# J1.net
KiCad netlist of a schematic drawn in Altium Designer
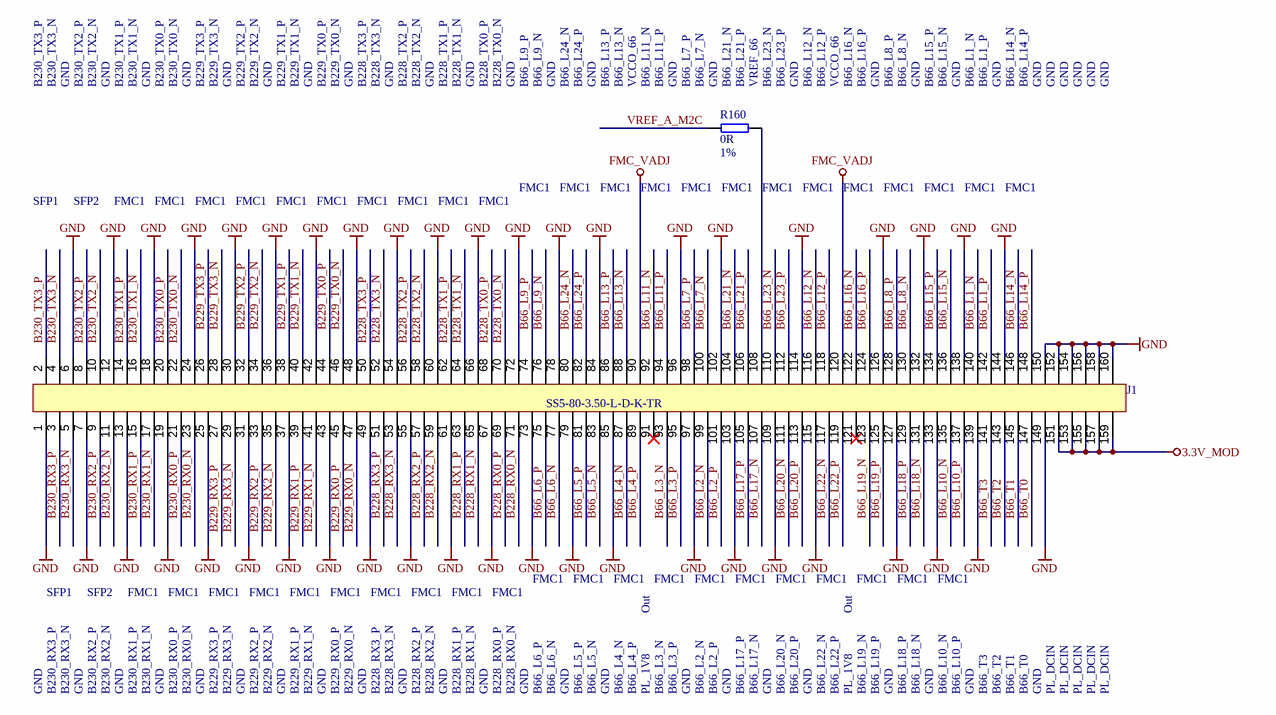
[diagram p0: J1.schdoc]

(export (version "E")
  (design (tool "Eeschema 10.0.6"))
  (components
    (comp (ref "J1")
      (value "SS5-80-3.50-L-D-K-TR")
      (footprint "SS5-80-3.50-L-D-K-TR")
      (description "Samtec Ultra Fine Pitch Socket REF192552-01, 160 Pins")
      (libsource (lib "TE") (part "CON-160"))
    )
    (comp (ref "R160")
      (value "0R")
      (footprint "RESC1005X40N")
      (description "WID SMD 0R")
      (fields (field (name "TOLERANCE") "1%"))
      (libsource (lib "TE") (part "RES"))
    )
  )
  (nets
    (net (code "1") (name "/B66_L1_N") (class "Default")
      (node (ref "J1") (pin "140") (pinfunction "140_140") (pintype "passive"))
    )
    (net (code "2") (name "/B66_L1_P") (class "Default")
      (node (ref "J1") (pin "142") (pinfunction "142_142") (pintype "passive"))
    )
    (net (code "3") (name "/B66_L2_N") (class "Default")
      (node (ref "J1") (pin "99") (pinfunction "99_99") (pintype "passive"))
    )
    (net (code "4") (name "/B66_L2_P") (class "Default")
      (node (ref "J1") (pin "101") (pinfunction "101_101") (pintype "passive"))
    )
    (net (code "5") (name "/B66_L3_N") (class "Default")
      (node (ref "J1") (pin "93") (pinfunction "93_93") (pintype "passive"))
    )
    (net (code "6") (name "/B66_L3_P") (class "Default")
      (node (ref "J1") (pin "95") (pinfunction "95_95") (pintype "passive"))
    )
    (net (code "7") (name "/B66_L4_N") (class "Default")
      (node (ref "J1") (pin "87") (pinfunction "87_87") (pintype "passive"))
    )
    (net (code "8") (name "/B66_L4_P") (class "Default")
      (node (ref "J1") (pin "89") (pinfunction "89_89") (pintype "passive"))
    )
    (net (code "9") (name "/B66_L5_N") (class "Default")
      (node (ref "J1") (pin "83") (pinfunction "83_83") (pintype "passive"))
    )
    (net (code "10") (name "/B66_L5_P") (class "Default")
      (node (ref "J1") (pin "81") (pinfunction "81_81") (pintype "passive"))
    )
    (net (code "11") (name "/B66_L6_N") (class "Default")
      (node (ref "J1") (pin "77") (pinfunction "77_77") (pintype "passive"))
    )
    (net (code "12") (name "/B66_L6_P") (class "Default")
      (node (ref "J1") (pin "75") (pinfunction "75_75") (pintype "passive"))
    )
    (net (code "13") (name "/B66_L7_N") (class "Default")
      (node (ref "J1") (pin "100") (pinfunction "100_100") (pintype "passive"))
    )
    (net (code "14") (name "/B66_L7_P") (class "Default")
      (node (ref "J1") (pin "98") (pinfunction "98_98") (pintype "passive"))
    )
    (net (code "15") (name "/B66_L8_N") (class "Default")
      (node (ref "J1") (pin "130") (pinfunction "130_130") (pintype "passive"))
    )
    (net (code "16") (name "/B66_L8_P") (class "Default")
      (node (ref "J1") (pin "128") (pinfunction "128_128") (pintype "passive"))
    )
    (net (code "17") (name "/B66_L9_N") (class "Default")
      (node (ref "J1") (pin "76") (pinfunction "76_76") (pintype "passive"))
    )
    (net (code "18") (name "/B66_L9_P") (class "Default")
      (node (ref "J1") (pin "74") (pinfunction "74_74") (pintype "passive"))
    )
    (net (code "19") (name "/B66_L10_N") (class "Default")
      (node (ref "J1") (pin "135") (pinfunction "135_135") (pintype "passive"))
    )
    (net (code "20") (name "/B66_L10_P") (class "Default")
      (node (ref "J1") (pin "137") (pinfunction "137_137") (pintype "passive"))
    )
    (net (code "21") (name "/B66_L11_N") (class "Default")
      (node (ref "J1") (pin "92") (pinfunction "92_92") (pintype "passive"))
    )
    (net (code "22") (name "/B66_L11_P") (class "Default")
      (node (ref "J1") (pin "94") (pinfunction "94_94") (pintype "passive"))
    )
    (net (code "23") (name "/B66_L12_N") (class "Default")
      (node (ref "J1") (pin "116") (pinfunction "116_116") (pintype "passive"))
    )
    (net (code "24") (name "/B66_L12_P") (class "Default")
      (node (ref "J1") (pin "118") (pinfunction "118_118") (pintype "passive"))
    )
    (net (code "25") (name "/B66_L13_N") (class "Default")
      (node (ref "J1") (pin "88") (pinfunction "88_88") (pintype "passive"))
    )
    (net (code "26") (name "/B66_L13_P") (class "Default")
      (node (ref "J1") (pin "86") (pinfunction "86_86") (pintype "passive"))
    )
    (net (code "27") (name "/B66_L14_N") (class "Default")
      (node (ref "J1") (pin "146") (pinfunction "146_146") (pintype "passive"))
    )
    (net (code "28") (name "/B66_L14_P") (class "Default")
      (node (ref "J1") (pin "148") (pinfunction "148_148") (pintype "passive"))
    )
    (net (code "29") (name "/B66_L15_N") (class "Default")
      (node (ref "J1") (pin "136") (pinfunction "136_136") (pintype "passive"))
    )
    (net (code "30") (name "/B66_L15_P") (class "Default")
      (node (ref "J1") (pin "134") (pinfunction "134_134") (pintype "passive"))
    )
    (net (code "31") (name "/B66_L16_N") (class "Default")
      (node (ref "J1") (pin "122") (pinfunction "122_122") (pintype "passive"))
    )
    (net (code "32") (name "/B66_L16_P") (class "Default")
      (node (ref "J1") (pin "124") (pinfunction "124_124") (pintype "passive"))
    )
    (net (code "33") (name "/B66_L17_N") (class "Default")
      (node (ref "J1") (pin "107") (pinfunction "107_107") (pintype "passive"))
    )
    (net (code "34") (name "/B66_L17_P") (class "Default")
      (node (ref "J1") (pin "105") (pinfunction "105_105") (pintype "passive"))
    )
    (net (code "35") (name "/B66_L18_N") (class "Default")
      (node (ref "J1") (pin "131") (pinfunction "131_131") (pintype "passive"))
    )
    (net (code "36") (name "/B66_L18_P") (class "Default")
      (node (ref "J1") (pin "129") (pinfunction "129_129") (pintype "passive"))
    )
    (net (code "37") (name "/B66_L19_N") (class "Default")
      (node (ref "J1") (pin "123") (pinfunction "123_123") (pintype "passive"))
    )
    (net (code "38") (name "/B66_L19_P") (class "Default")
      (node (ref "J1") (pin "125") (pinfunction "125_125") (pintype "passive"))
    )
    (net (code "39") (name "/B66_L20_N") (class "Default")
      (node (ref "J1") (pin "111") (pinfunction "111_111") (pintype "passive"))
    )
    (net (code "40") (name "/B66_L20_P") (class "Default")
      (node (ref "J1") (pin "113") (pinfunction "113_113") (pintype "passive"))
    )
    (net (code "41") (name "/B66_L21_N") (class "Default")
      (node (ref "J1") (pin "104") (pinfunction "104_104") (pintype "passive"))
    )
    (net (code "42") (name "/B66_L21_P") (class "Default")
      (node (ref "J1") (pin "106") (pinfunction "106_106") (pintype "passive"))
    )
    (net (code "43") (name "/B66_L22_N") (class "Default")
      (node (ref "J1") (pin "117") (pinfunction "117_117") (pintype "passive"))
    )
    (net (code "44") (name "/B66_L22_P") (class "Default")
      (node (ref "J1") (pin "119") (pinfunction "119_119") (pintype "passive"))
    )
    (net (code "45") (name "/B66_L23_N") (class "Default")
      (node (ref "J1") (pin "110") (pinfunction "110_110") (pintype "passive"))
    )
    (net (code "46") (name "/B66_L23_P") (class "Default")
      (node (ref "J1") (pin "112") (pinfunction "112_112") (pintype "passive"))
    )
    (net (code "47") (name "/B66_L24_N") (class "Default")
      (node (ref "J1") (pin "80") (pinfunction "80_80") (pintype "passive"))
    )
    (net (code "48") (name "/B66_L24_P") (class "Default")
      (node (ref "J1") (pin "82") (pinfunction "82_82") (pintype "passive"))
    )
    (net (code "49") (name "/B66_T0") (class "Default")
      (node (ref "J1") (pin "147") (pinfunction "147_147") (pintype "passive"))
    )
    (net (code "50") (name "/B66_T1") (class "Default")
      (node (ref "J1") (pin "145") (pinfunction "145_145") (pintype "passive"))
    )
    (net (code "51") (name "/B66_T2") (class "Default")
      (node (ref "J1") (pin "143") (pinfunction "143_143") (pintype "passive"))
    )
    (net (code "52") (name "/B66_T3") (class "Default")
      (node (ref "J1") (pin "141") (pinfunction "141_141") (pintype "passive"))
    )
    (net (code "53") (name "/B228_RX0_N") (class "Default")
      (node (ref "J1") (pin "71") (pinfunction "71_71") (pintype "passive"))
    )
    (net (code "54") (name "/B228_RX0_P") (class "Default")
      (node (ref "J1") (pin "69") (pinfunction "69_69") (pintype "passive"))
    )
    (net (code "55") (name "/B228_RX1_N") (class "Default")
      (node (ref "J1") (pin "65") (pinfunction "65_65") (pintype "passive"))
    )
    (net (code "56") (name "/B228_RX1_P") (class "Default")
      (node (ref "J1") (pin "63") (pinfunction "63_63") (pintype "passive"))
    )
    (net (code "57") (name "/B228_RX2_N") (class "Default")
      (node (ref "J1") (pin "59") (pinfunction "59_59") (pintype "passive"))
    )
    (net (code "58") (name "/B228_RX2_P") (class "Default")
      (node (ref "J1") (pin "57") (pinfunction "57_57") (pintype "passive"))
    )
    (net (code "59") (name "/B228_RX3_N") (class "Default")
      (node (ref "J1") (pin "53") (pinfunction "53_53") (pintype "passive"))
    )
    (net (code "60") (name "/B228_RX3_P") (class "Default")
      (node (ref "J1") (pin "51") (pinfunction "51_51") (pintype "passive"))
    )
    (net (code "61") (name "/B228_TX0_N") (class "Default")
      (node (ref "J1") (pin "70") (pinfunction "70_70") (pintype "passive"))
    )
    (net (code "62") (name "/B228_TX0_P") (class "Default")
      (node (ref "J1") (pin "68") (pinfunction "68_68") (pintype "passive"))
    )
    (net (code "63") (name "/B228_TX1_N") (class "Default")
      (node (ref "J1") (pin "64") (pinfunction "64_64") (pintype "passive"))
    )
    (net (code "64") (name "/B228_TX1_P") (class "Default")
      (node (ref "J1") (pin "62") (pinfunction "62_62") (pintype "passive"))
    )
    (net (code "65") (name "/B228_TX2_N") (class "Default")
      (node (ref "J1") (pin "58") (pinfunction "58_58") (pintype "passive"))
    )
    (net (code "66") (name "/B228_TX2_P") (class "Default")
      (node (ref "J1") (pin "56") (pinfunction "56_56") (pintype "passive"))
    )
    (net (code "67") (name "/B228_TX3_N") (class "Default")
      (node (ref "J1") (pin "52") (pinfunction "52_52") (pintype "passive"))
    )
    (net (code "68") (name "/B228_TX3_P") (class "Default")
      (node (ref "J1") (pin "50") (pinfunction "50_50") (pintype "passive"))
    )
    (net (code "69") (name "/B229_RX0_N") (class "Default")
      (node (ref "J1") (pin "47") (pinfunction "47_47") (pintype "passive"))
    )
    (net (code "70") (name "/B229_RX0_P") (class "Default")
      (node (ref "J1") (pin "45") (pinfunction "45_45") (pintype "passive"))
    )
    (net (code "71") (name "/B229_RX1_N") (class "Default")
      (node (ref "J1") (pin "41") (pinfunction "41_41") (pintype "passive"))
    )
    (net (code "72") (name "/B229_RX1_P") (class "Default")
      (node (ref "J1") (pin "39") (pinfunction "39_39") (pintype "passive"))
    )
    (net (code "73") (name "/B229_RX2_N") (class "Default")
      (node (ref "J1") (pin "35") (pinfunction "35_35") (pintype "passive"))
    )
    (net (code "74") (name "/B229_RX2_P") (class "Default")
      (node (ref "J1") (pin "33") (pinfunction "33_33") (pintype "passive"))
    )
    (net (code "75") (name "/B229_RX3_N") (class "Default")
      (node (ref "J1") (pin "29") (pinfunction "29_29") (pintype "passive"))
    )
    (net (code "76") (name "/B229_RX3_P") (class "Default")
      (node (ref "J1") (pin "27") (pinfunction "27_27") (pintype "passive"))
    )
    (net (code "77") (name "/B229_TX0_N") (class "Default")
      (node (ref "J1") (pin "46") (pinfunction "46_46") (pintype "passive"))
    )
    (net (code "78") (name "/B229_TX0_P") (class "Default")
      (node (ref "J1") (pin "44") (pinfunction "44_44") (pintype "passive"))
    )
    (net (code "79") (name "/B229_TX1_N") (class "Default")
      (node (ref "J1") (pin "40") (pinfunction "40_40") (pintype "passive"))
    )
    (net (code "80") (name "/B229_TX1_P") (class "Default")
      (node (ref "J1") (pin "38") (pinfunction "38_38") (pintype "passive"))
    )
    (net (code "81") (name "/B229_TX2_N") (class "Default")
      (node (ref "J1") (pin "34") (pinfunction "34_34") (pintype "passive"))
    )
    (net (code "82") (name "/B229_TX2_P") (class "Default")
      (node (ref "J1") (pin "32") (pinfunction "32_32") (pintype "passive"))
    )
    (net (code "83") (name "/B229_TX3_N") (class "Default")
      (node (ref "J1") (pin "28") (pinfunction "28_28") (pintype "passive"))
    )
    (net (code "84") (name "/B229_TX3_P") (class "Default")
      (node (ref "J1") (pin "26") (pinfunction "26_26") (pintype "passive"))
    )
    (net (code "85") (name "/B230_RX0_N") (class "Default")
      (node (ref "J1") (pin "23") (pinfunction "23_23") (pintype "passive"))
    )
    (net (code "86") (name "/B230_RX0_P") (class "Default")
      (node (ref "J1") (pin "21") (pinfunction "21_21") (pintype "passive"))
    )
    (net (code "87") (name "/B230_RX1_N") (class "Default")
      (node (ref "J1") (pin "17") (pinfunction "17_17") (pintype "passive"))
    )
    (net (code "88") (name "/B230_RX1_P") (class "Default")
      (node (ref "J1") (pin "15") (pinfunction "15_15") (pintype "passive"))
    )
    (net (code "89") (name "/B230_RX2_N") (class "Default")
      (node (ref "J1") (pin "11") (pinfunction "11_11") (pintype "passive"))
    )
    (net (code "90") (name "/B230_RX2_P") (class "Default")
      (node (ref "J1") (pin "9") (pinfunction "9_9") (pintype "passive"))
    )
    (net (code "91") (name "/B230_RX3_N") (class "Default")
      (node (ref "J1") (pin "5") (pinfunction "5_5") (pintype "passive"))
    )
    (net (code "92") (name "/B230_RX3_P") (class "Default")
      (node (ref "J1") (pin "3") (pinfunction "3_3") (pintype "passive"))
    )
    (net (code "93") (name "/B230_TX0_N") (class "Default")
      (node (ref "J1") (pin "22") (pinfunction "22_22") (pintype "passive"))
    )
    (net (code "94") (name "/B230_TX0_P") (class "Default")
      (node (ref "J1") (pin "20") (pinfunction "20_20") (pintype "passive"))
    )
    (net (code "95") (name "/B230_TX1_N") (class "Default")
      (node (ref "J1") (pin "16") (pinfunction "16_16") (pintype "passive"))
    )
    (net (code "96") (name "/B230_TX1_P") (class "Default")
      (node (ref "J1") (pin "14") (pinfunction "14_14") (pintype "passive"))
    )
    (net (code "97") (name "/B230_TX2_N") (class "Default")
      (node (ref "J1") (pin "10") (pinfunction "10_10") (pintype "passive"))
    )
    (net (code "98") (name "/B230_TX2_P") (class "Default")
      (node (ref "J1") (pin "8") (pinfunction "8_8") (pintype "passive"))
    )
    (net (code "99") (name "/B230_TX3_N") (class "Default")
      (node (ref "J1") (pin "4") (pinfunction "4_4") (pintype "passive"))
    )
    (net (code "100") (name "/B230_TX3_P") (class "Default")
      (node (ref "J1") (pin "2") (pinfunction "2_2") (pintype "passive"))
    )
    (net (code "101") (name "/VREF_A_M2C") (class "Default")
      (node (ref "R160") (pin "2") (pinfunction "2_2") (pintype "passive"))
    )
    (net (code "102") (name "3.3V_MOD") (class "Default")
      (node (ref "J1") (pin "151") (pinfunction "151_151") (pintype "passive"))
      (node (ref "J1") (pin "153") (pinfunction "153_153") (pintype "passive"))
      (node (ref "J1") (pin "155") (pinfunction "155_155") (pintype "passive"))
      (node (ref "J1") (pin "157") (pinfunction "157_157") (pintype "passive"))
      (node (ref "J1") (pin "159") (pinfunction "159_159") (pintype "passive"))
    )
    (net (code "103") (name "FMC_VADJ") (class "Default")
      (node (ref "J1") (pin "120") (pinfunction "120_120") (pintype "passive"))
      (node (ref "J1") (pin "90") (pinfunction "90_90") (pintype "passive"))
    )
    (net (code "104") (name "GND") (class "Default")
      (node (ref "J1") (pin "1") (pinfunction "1_1") (pintype "passive"))
      (node (ref "J1") (pin "102") (pinfunction "102_102") (pintype "passive"))
      (node (ref "J1") (pin "103") (pinfunction "103_103") (pintype "passive"))
      (node (ref "J1") (pin "109") (pinfunction "109_109") (pintype "passive"))
      (node (ref "J1") (pin "114") (pinfunction "114_114") (pintype "passive"))
      (node (ref "J1") (pin "115") (pinfunction "115_115") (pintype "passive"))
      (node (ref "J1") (pin "12") (pinfunction "12_12") (pintype "passive"))
      (node (ref "J1") (pin "126") (pinfunction "126_126") (pintype "passive"))
      (node (ref "J1") (pin "127") (pinfunction "127_127") (pintype "passive"))
      (node (ref "J1") (pin "13") (pinfunction "13_13") (pintype "passive"))
      (node (ref "J1") (pin "132") (pinfunction "132_132") (pintype "passive"))
      (node (ref "J1") (pin "133") (pinfunction "133_133") (pintype "passive"))
      (node (ref "J1") (pin "138") (pinfunction "138_138") (pintype "passive"))
      (node (ref "J1") (pin "139") (pinfunction "139_139") (pintype "passive"))
      (node (ref "J1") (pin "144") (pinfunction "144_144") (pintype "passive"))
      (node (ref "J1") (pin "149") (pinfunction "149_149") (pintype "passive"))
      (node (ref "J1") (pin "150") (pinfunction "150_150") (pintype "passive"))
      (node (ref "J1") (pin "152") (pinfunction "152_152") (pintype "passive"))
      (node (ref "J1") (pin "154") (pinfunction "154_154") (pintype "passive"))
      (node (ref "J1") (pin "156") (pinfunction "156_156") (pintype "passive"))
      (node (ref "J1") (pin "158") (pinfunction "158_158") (pintype "passive"))
      (node (ref "J1") (pin "160") (pinfunction "160_160") (pintype "passive"))
      (node (ref "J1") (pin "18") (pinfunction "18_18") (pintype "passive"))
      (node (ref "J1") (pin "19") (pinfunction "19_19") (pintype "passive"))
      (node (ref "J1") (pin "24") (pinfunction "24_24") (pintype "passive"))
      (node (ref "J1") (pin "25") (pinfunction "25_25") (pintype "passive"))
      (node (ref "J1") (pin "30") (pinfunction "30_30") (pintype "passive"))
      (node (ref "J1") (pin "31") (pinfunction "31_31") (pintype "passive"))
      (node (ref "J1") (pin "36") (pinfunction "36_36") (pintype "passive"))
      (node (ref "J1") (pin "37") (pinfunction "37_37") (pintype "passive"))
      (node (ref "J1") (pin "42") (pinfunction "42_42") (pintype "passive"))
      (node (ref "J1") (pin "43") (pinfunction "43_43") (pintype "passive"))
      (node (ref "J1") (pin "48") (pinfunction "48_48") (pintype "passive"))
      (node (ref "J1") (pin "49") (pinfunction "49_49") (pintype "passive"))
      (node (ref "J1") (pin "54") (pinfunction "54_54") (pintype "passive"))
      (node (ref "J1") (pin "55") (pinfunction "55_55") (pintype "passive"))
      (node (ref "J1") (pin "6") (pinfunction "6_6") (pintype "passive"))
      (node (ref "J1") (pin "60") (pinfunction "60_60") (pintype "passive"))
      (node (ref "J1") (pin "61") (pinfunction "61_61") (pintype "passive"))
      (node (ref "J1") (pin "66") (pinfunction "66_66") (pintype "passive"))
      (node (ref "J1") (pin "67") (pinfunction "67_67") (pintype "passive"))
      (node (ref "J1") (pin "7") (pinfunction "7_7") (pintype "passive"))
      (node (ref "J1") (pin "72") (pinfunction "72_72") (pintype "passive"))
      (node (ref "J1") (pin "73") (pinfunction "73_73") (pintype "passive"))
      (node (ref "J1") (pin "78") (pinfunction "78_78") (pintype "passive"))
      (node (ref "J1") (pin "79") (pinfunction "79_79") (pintype "passive"))
      (node (ref "J1") (pin "84") (pinfunction "84_84") (pintype "passive"))
      (node (ref "J1") (pin "85") (pinfunction "85_85") (pintype "passive"))
      (node (ref "J1") (pin "96") (pinfunction "96_96") (pintype "passive"))
      (node (ref "J1") (pin "97") (pinfunction "97_97") (pintype "passive"))
    )
    (net (code "105") (name "Net-(J1-Pad108)") (class "Default")
      (node (ref "J1") (pin "108") (pinfunction "108_108") (pintype "passive"))
      (node (ref "R160") (pin "1") (pinfunction "1_1") (pintype "passive"))
    )
    (net (code "106") (name "unconnected-(J1-Pad91)") (class "Default")
      (node (ref "J1") (pin "91") (pinfunction "91_91") (pintype "passive+no_connect"))
    )
    (net (code "107") (name "unconnected-(J1-Pad121)") (class "Default")
      (node (ref "J1") (pin "121") (pinfunction "121_121") (pintype "passive+no_connect"))
    )
  )
)
